# 12V_Buck_For_LDOs.net
KiCad netlist of a schematic drawn in Altium Designer
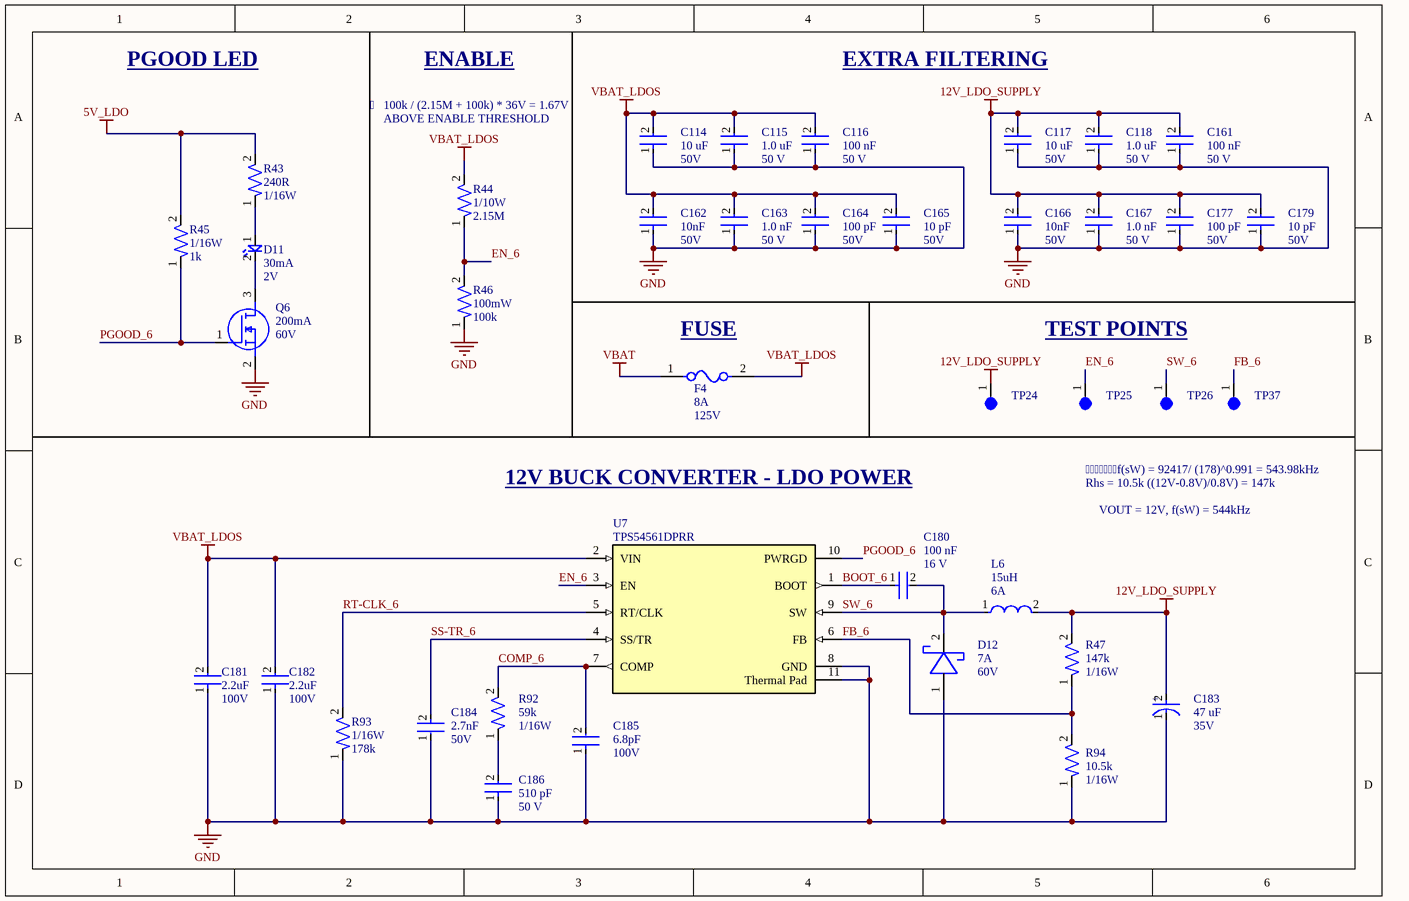
[diagram p0: 12V_Buck_For_LDOs.SchDoc]

(export (version "E")
  (design (tool "Eeschema 10.0.6"))
  (components
    (comp (ref "C114")
      (value "CL32B106KBJNNNE")
      (footprint "CAP-1210")
      (description "CAP CER 10UF 50V X7R 1210")
      (fields (field (name "VOLTAGE") "50V") (field (name "CAPACITANCE") "10 uF"))
      (libsource (lib "JLC_25") (part "CAP-10U-0002"))
    )
    (comp (ref "C115")
      (value "CC0805KKX7R9BB105")
      (footprint "CAP-0805")
      (description "CAP CER 1UF 50V X7R 0805")
      (fields (field (name "VOLTAGE") "50 V") (field (name "CAPACITANCE") "1.0 uF"))
      (libsource (lib "JLC_25") (part "CAP-1U-0001"))
    )
    (comp (ref "C116")
      (value "CC0805KRX7R9BB104")
      (footprint "CAP-0805")
      (description "CAP CER 0.1UF 50V X7R 0805")
      (fields (field (name "VOLTAGE RATING") "50 V") (field (name "CAPACITANCE") "100 nF"))
      (libsource (lib "JLC_25") (part "CAP-0.1U-0002"))
    )
    (comp (ref "C117")
      (value "CL32B106KBJNNNE")
      (footprint "CAP-1210")
      (description "CAP CER 10UF 50V X7R 1210")
      (fields (field (name "VOLTAGE") "50V") (field (name "CAPACITANCE") "10 uF"))
      (libsource (lib "JLC_25") (part "CAP-10U-0002"))
    )
    (comp (ref "C118")
      (value "CC0805KKX7R9BB105")
      (footprint "CAP-0805")
      (description "CAP CER 1UF 50V X7R 0805")
      (fields (field (name "VOLTAGE") "50 V") (field (name "CAPACITANCE") "1.0 uF"))
      (libsource (lib "JLC_25") (part "CAP-1U-0001"))
    )
    (comp (ref "C161")
      (value "CC0805KRX7R9BB104")
      (footprint "CAP-0805")
      (description "CAP CER 0.1UF 50V X7R 0805")
      (fields (field (name "VOLTAGE RATING") "50 V") (field (name "CAPACITANCE") "100 nF"))
      (libsource (lib "JLC_25") (part "CAP-0.1U-0002"))
    )
    (comp (ref "C162")
      (value "GRM2195C1H103JA01D")
      (footprint "CAP-0805")
      (description "CAP CER 10000PF 50V C0G/NP0 0805")
      (fields (field (name "VOLTAGE") "50V") (field (name "CAPACITANCE") "10nF"))
      (libsource (lib "JLC_25") (part "CAP-10N-0001"))
    )
    (comp (ref "C163")
      (value "CC0402KRX7R9BB102")
      (footprint "CAP-0402")
      (description "CAP CER 1000PF 50V X7R 0402")
      (fields (field (name "VOLTAGE") "50 V") (field (name "CAPACITANCE") "1.0 nF"))
      (libsource (lib "JLC_25") (part "CAP-1N-0001"))
    )
    (comp (ref "C164")
      (value "CC0402JRNPO9BN101")
      (footprint "CAP-0402")
      (description "CAP CER 100PF 50V C0G/NPO 0402")
      (fields (field (name "CAPACITANCE") "100 pF") (field (name "VOLTAGE") "50V"))
      (libsource (lib "JLC_25") (part "CAP-100P-0001"))
    )
    (comp (ref "C165")
      (value "CC0402JRNPO9BN100")
      (footprint "CAP-0402")
      (description "CAP CER 10PF 50V C0G/NPO 0402")
      (fields (field (name "CAPACITANCE") "10 pF") (field (name "VOLTAGE") "50V"))
      (libsource (lib "JLC_25") (part "CAP-10P-0001"))
    )
    (comp (ref "C166")
      (value "GRM2195C1H103JA01D")
      (footprint "CAP-0805")
      (description "CAP CER 10000PF 50V C0G/NP0 0805")
      (fields (field (name "VOLTAGE") "50V") (field (name "CAPACITANCE") "10nF"))
      (libsource (lib "JLC_25") (part "CAP-10N-0001"))
    )
    (comp (ref "C167")
      (value "CC0402KRX7R9BB102")
      (footprint "CAP-0402")
      (description "CAP CER 1000PF 50V X7R 0402")
      (fields (field (name "VOLTAGE") "50 V") (field (name "CAPACITANCE") "1.0 nF"))
      (libsource (lib "JLC_25") (part "CAP-1N-0001"))
    )
    (comp (ref "C177")
      (value "CC0402JRNPO9BN101")
      (footprint "CAP-0402")
      (description "CAP CER 100PF 50V C0G/NPO 0402")
      (fields (field (name "CAPACITANCE") "100 pF") (field (name "VOLTAGE") "50V"))
      (libsource (lib "JLC_25") (part "CAP-100P-0001"))
    )
    (comp (ref "C179")
      (value "CC0402JRNPO9BN100")
      (footprint "CAP-0402")
      (description "CAP CER 10PF 50V C0G/NPO 0402")
      (fields (field (name "CAPACITANCE") "10 pF") (field (name "VOLTAGE") "50V"))
      (libsource (lib "JLC_25") (part "CAP-10P-0001"))
    )
    (comp (ref "C180")
      (value "CC0402KRX7R7BB104")
      (footprint "CAP-0402")
      (description "CAP CER 0.1UF 16V X7R 0402")
      (fields (field (name "VOLTAGE RATING") "16 V") (field (name "CAPACITANCE") "100 nF"))
      (libsource (lib "JLC_25") (part "CAP-0.1U-0001"))
    )
    (comp (ref "C181")
      (value "CC1206KKX7R0BB225")
      (footprint "CAP-1206")
      (description "CAP CER 2.2UF 100V X7R 1206")
      (fields (field (name "CAPACITANCE") "2.2uF") (field (name "VOLTAGE") "100V"))
      (libsource (lib "JLC_25") (part "CAP-2.2U-0001"))
    )
    (comp (ref "C182")
      (value "CC1206KKX7R0BB225")
      (footprint "CAP-1206")
      (description "CAP CER 2.2UF 100V X7R 1206")
      (fields (field (name "CAPACITANCE") "2.2uF") (field (name "VOLTAGE") "100V"))
      (libsource (lib "JLC_25") (part "CAP-2.2U-0001"))
    )
    (comp (ref "C183")
      (value "EEH-ZC1V470P")
      (footprint "CAP_EEHZC1V470P")
      (description "47 µF 35 V Aluminum - Polymer Capacitors Radial, Can - SMD 60mOhm 4000 Hrs @ 125°C")
      (fields (field (name "VOLTAGE") "35V") (field (name "CAPACITANCE") "47 uF"))
      (libsource (lib "JLC_25") (part "CAP-47U-0003"))
    )
    (comp (ref "C184")
      (value "GRM2165C1H272JA01D")
      (footprint "CAP-0805")
      (description "CAP CER 2700PF 50V C0G/NP0 0805")
      (fields (field (name "VOLTAGE") "50V") (field (name "CAPACITANCE") "2.7nF"))
      (libsource (lib "JLC_25") (part "CAP-2.7N-0001"))
    )
    (comp (ref "C185")
      (value "CC0603CRNPO0BN6R8")
      (footprint "CAP-0603")
      (description "CAP CER 6.8PF 100V C0G/NPO 0603")
      (fields (field (name "VOLTAGE") "100V") (field (name "CAPACITANCE") "6.8pF"))
      (libsource (lib "JLC_25") (part "CAP-6.8P-0001"))
    )
    (comp (ref "C186")
      (value "0402N511J500CT")
      (footprint "CAP-0402")
      (description "CAP CER 510PF 50V C0G/NP0 0402")
      (fields (field (name "VOLTAGE") "50 V") (field (name "CAPACITANCE") "510 pF"))
      (libsource (lib "JLC_25") (part "CAP-510P-0001"))
    )
    (comp (ref "D11")
      (value "BL-HKC36G-AV-TRB")
      (footprint "LED-0603")
      (description "LED YELLOW CLEAR 0603 SMD")
      (fields (field (name "FORWARD CURRENT") "30mA") (field (name "FORWARD VOLTAGE") "2V"))
      (libsource (lib "JLC_25") (part "LED-0001"))
    )
    (comp (ref "D12")
      (value "PDS760-13")
      (footprint "DO-POWERDI5")
      (description "DIODE SCHOTTKY 60V 7A POWERDI5")
      (fields (field (name "FORWARD CURRENT") "7A") (field (name "REVERSE VOLTAGE (DC)") "60V"))
      (libsource (lib "JLC_25") (part "DIO-SCHOTTKY-0001"))
    )
    (comp (ref "F4")
      (value "01550900M")
      (footprint "FUSE-0001")
      (description "FUSE BLOK CARTRIDGE 125V 10A SMD")
      (fields (field (name "FUSE CURRENT") "8A") (field (name "VOLTAGE RATING") "125V"))
      (libsource (lib "JLC_25") (part "FUSE-0001"))
    )
    (comp (ref "L6")
      (value "CSAD1010-150M")
      (footprint "IND-15U-0002")
      (description "SMD MOLDING POWER CHOKE")
      (fields (field (name "INDUCTANCE") "15uH") (field (name "CURRENT RATING") "6A"))
      (libsource (lib "JLC_25") (part "IND-15U-0002-NoJLC"))
    )
    (comp (ref "Q6")
      (value "T2N7002AK,LM")
      (footprint "IC-SOT23-3")
      (description "MOSFET N-CH 60V 200MA SOT23")
      (fields (field (name "CONTINUOUS CURRENT") "200mA") (field (name "VOLTAGE") "60V"))
      (libsource (lib "JLC_25") (part "NMOS-200MA-0001"))
    )
    (comp (ref "R43")
      (value "RC0402FR-07240RL")
      (footprint "RES-0402")
      (description "240R 0.063W 1% 0402 (1005 Metric)  SMD")
      (fields
        (field (name "TOLERANCE") "1%")
        (field (name "RESISTANCE") "240R")
        (field (name "POWER") "1/16W")
      )
      (libsource (lib "JLC_25") (part "RES-240-0001"))
    )
    (comp (ref "R44")
      (value "RC0603FR-072M15L")
      (footprint "RES-0603")
      (description "RES SMD 2.15M OHM 1% 1/10W 0603")
      (fields
        (field (name "TOLERANCE") "1%")
        (field (name "POWER") "1/10W")
        (field (name "RESISTANCE") "2.15M")
      )
      (libsource (lib "JLC_25") (part "RES-2.15M-0001"))
    )
    (comp (ref "R45")
      (value "RC0402FR-071KL")
      (footprint "RES-0402")
      (description "RES 1K OHM 1% 1/16W 0402")
      (fields (field (name "TOLERANCE") "1%") (field (name "POWER") "1/16W") (field (name "RESISTANCE") "1k"))
      (libsource (lib "JLC_25") (part "RES-1k-0001"))
    )
    (comp (ref "R46")
      (value "RC0603FR-07100KL")
      (footprint "RES-0603")
      (description "RES SMD 100K OHM 1% 1/10W 0603")
      (fields
        (field (name "TOLERANCE") "1%")
        (field (name "POWER") "100mW")
        (field (name "RESISTANCE") "100k")
      )
      (libsource (lib "JLC_25") (part "RES-100k-0001"))
    )
    (comp (ref "R47")
      (value "RC0402FR-07147KL")
      (footprint "RES-0402")
      (description "RES 147K OHM 1% 1/16W 0402")
      (fields
        (field (name "TOLERANCE") "1%")
        (field (name "POWER") "1/16W")
        (field (name "RESISTANCE") "147k")
      )
      (libsource (lib "JLC_25") (part "RES-147k-0001"))
    )
    (comp (ref "R92")
      (value "RC0402FR-0759KL")
      (footprint "RES-0402")
      (description "RES 59K OHM 1% 1/16W 0402")
      (fields
        (field (name "TOLERANCE") "1%")
        (field (name "POWER") "1/16W")
        (field (name "RESISTANCE") "59k")
      )
      (libsource (lib "JLC_25") (part "RES-59k-0001"))
    )
    (comp (ref "R93")
      (value "RTT021783FTH")
      (footprint "RES-0402")
      (description "62.5mW Thick Film Resistors 50V ±100ppm/℃ ±1% 178kΩ 0402 Chip Resistor - Surface Mount ROHS")
      (fields
        (field (name "TOLERANCE") "1%")
        (field (name "POWER") "1/16W")
        (field (name "RESISTANCE") "178k")
      )
      (libsource (lib "JLC_25") (part "RES-178k-0001_1"))
    )
    (comp (ref "R94")
      (value "RC0402FR-0710K5L")
      (footprint "RES-0402")
      (description "RES 10.5K OHM 1% 1/16W 0402")
      (fields
        (field (name "TOLERANCE") "1%")
        (field (name "POWER") "1/16W")
        (field (name "RESISTANCE") "10.5k")
      )
      (libsource (lib "JLC_25") (part "RES-10.5k-0001"))
    )
    (comp (ref "TP24")
      (value "5003")
      (footprint "TEST-POINT-0001")
      (description "Oranange PC Test Point, Miniature Phoisphor Bronze Silver Plating Through Hole Mounting Type")
      (libsource (lib "*") (part "TEST-POINT-0001"))
    )
    (comp (ref "TP25")
      (value "5003")
      (footprint "TEST-POINT-0001")
      (description "Oranange PC Test Point, Miniature Phoisphor Bronze Silver Plating Through Hole Mounting Type")
      (libsource (lib "*") (part "TEST-POINT-0001"))
    )
    (comp (ref "TP26")
      (value "5003")
      (footprint "TEST-POINT-0001")
      (description "Oranange PC Test Point, Miniature Phoisphor Bronze Silver Plating Through Hole Mounting Type")
      (libsource (lib "*") (part "TEST-POINT-0001"))
    )
    (comp (ref "TP37")
      (value "5003")
      (footprint "TEST-POINT-0001")
      (description "Oranange PC Test Point, Miniature Phoisphor Bronze Silver Plating Through Hole Mounting Type")
      (libsource (lib "*") (part "TEST-POINT-0001"))
    )
    (comp (ref "U7")
      (value "TPS54561DPRR")
      (footprint "IC-10WSON")
      (description "IC REG BUCK ADJ 5A 10WSON")
      (libsource (lib "JLC_25") (part "IC-BUCK-0001"))
    )
  )
  (nets
    (net (code "1") (name "/BOOT_6") (class "Default")
      (node (ref "C180") (pin "1") (pinfunction "1_1") (pintype "passive"))
      (node (ref "U7") (pin "1") (pinfunction "BOOT_1") (pintype "output"))
    )
    (net (code "2") (name "/COMP_6") (class "Default")
      (node (ref "C185") (pin "2") (pinfunction "2_2") (pintype "passive"))
      (node (ref "R92") (pin "2") (pinfunction "2_2") (pintype "passive"))
      (node (ref "U7") (pin "7") (pinfunction "COMP_7") (pintype "output"))
    )
    (net (code "3") (name "/EN_6") (class "Default")
      (node (ref "R44") (pin "1") (pinfunction "1_1") (pintype "passive"))
      (node (ref "R46") (pin "2") (pinfunction "2_2") (pintype "passive"))
      (node (ref "TP25") (pin "1") (pinfunction "0_1") (pintype "passive"))
      (node (ref "U7") (pin "3") (pinfunction "EN_3") (pintype "input"))
    )
    (net (code "4") (name "/FB_6") (class "Default")
      (node (ref "R47") (pin "1") (pinfunction "1_1") (pintype "passive"))
      (node (ref "R94") (pin "2") (pinfunction "2_2") (pintype "passive"))
      (node (ref "TP37") (pin "1") (pinfunction "0_1") (pintype "passive"))
      (node (ref "U7") (pin "6") (pinfunction "FB_6") (pintype "input"))
    )
    (net (code "5") (name "/PGOOD_6") (class "Default")
      (node (ref "Q6") (pin "1") (pinfunction "G_1") (pintype "passive"))
      (node (ref "R45") (pin "1") (pinfunction "1_1") (pintype "passive"))
      (node (ref "U7") (pin "10") (pinfunction "PWRGD_10") (pintype "open_collector"))
    )
    (net (code "6") (name "/RT-CLK_6") (class "Default")
      (node (ref "R93") (pin "2") (pinfunction "2_2") (pintype "passive"))
      (node (ref "U7") (pin "5") (pinfunction "RT/CLK_5") (pintype "input"))
    )
    (net (code "7") (name "/SS-TR_6") (class "Default")
      (node (ref "C184") (pin "2") (pinfunction "2_2") (pintype "passive"))
      (node (ref "U7") (pin "4") (pinfunction "SS/TR_4") (pintype "input"))
    )
    (net (code "8") (name "/SW_6") (class "Default")
      (node (ref "C180") (pin "2") (pinfunction "2_2") (pintype "passive"))
      (node (ref "D12") (pin "2") (pinfunction "ANODE_2") (pintype "passive"))
      (node (ref "L6") (pin "1") (pinfunction "1_1") (pintype "passive"))
      (node (ref "TP26") (pin "1") (pinfunction "0_1") (pintype "passive"))
      (node (ref "U7") (pin "9") (pinfunction "SW_9") (pintype "input"))
    )
    (net (code "9") (name "5V_LDO") (class "Default")
      (node (ref "R43") (pin "2") (pinfunction "2_2") (pintype "passive"))
      (node (ref "R45") (pin "2") (pinfunction "2_2") (pintype "passive"))
    )
    (net (code "10") (name "12V_LDO_SUPPLY") (class "Default")
      (node (ref "C117") (pin "2") (pinfunction "2_2") (pintype "passive"))
      (node (ref "C118") (pin "2") (pinfunction "2_2") (pintype "passive"))
      (node (ref "C161") (pin "2") (pinfunction "2_2") (pintype "passive"))
      (node (ref "C166") (pin "2") (pinfunction "2_2") (pintype "passive"))
      (node (ref "C167") (pin "2") (pinfunction "2_2") (pintype "passive"))
      (node (ref "C177") (pin "2") (pinfunction "2_2") (pintype "passive"))
      (node (ref "C179") (pin "2") (pinfunction "2_2") (pintype "passive"))
      (node (ref "C183") (pin "2") (pinfunction "A_2") (pintype "passive"))
      (node (ref "L6") (pin "2") (pinfunction "2_2") (pintype "passive"))
      (node (ref "R47") (pin "2") (pinfunction "2_2") (pintype "passive"))
      (node (ref "TP24") (pin "1") (pinfunction "0_1") (pintype "passive"))
    )
    (net (code "11") (name "GND") (class "Default")
      (node (ref "C114") (pin "1") (pinfunction "1_1") (pintype "passive"))
      (node (ref "C115") (pin "1") (pinfunction "1_1") (pintype "passive"))
      (node (ref "C116") (pin "1") (pinfunction "1_1") (pintype "passive"))
      (node (ref "C117") (pin "1") (pinfunction "1_1") (pintype "passive"))
      (node (ref "C118") (pin "1") (pinfunction "1_1") (pintype "passive"))
      (node (ref "C161") (pin "1") (pinfunction "1_1") (pintype "passive"))
      (node (ref "C162") (pin "1") (pinfunction "1_1") (pintype "passive"))
      (node (ref "C163") (pin "1") (pinfunction "1_1") (pintype "passive"))
      (node (ref "C164") (pin "1") (pinfunction "1_1") (pintype "passive"))
      (node (ref "C165") (pin "1") (pinfunction "1_1") (pintype "passive"))
      (node (ref "C166") (pin "1") (pinfunction "1_1") (pintype "passive"))
      (node (ref "C167") (pin "1") (pinfunction "1_1") (pintype "passive"))
      (node (ref "C177") (pin "1") (pinfunction "1_1") (pintype "passive"))
      (node (ref "C179") (pin "1") (pinfunction "1_1") (pintype "passive"))
      (node (ref "C181") (pin "1") (pinfunction "1_1") (pintype "passive"))
      (node (ref "C182") (pin "1") (pinfunction "1_1") (pintype "passive"))
      (node (ref "C183") (pin "1") (pinfunction "C_1") (pintype "passive"))
      (node (ref "C184") (pin "1") (pinfunction "1_1") (pintype "passive"))
      (node (ref "C185") (pin "1") (pinfunction "1_1") (pintype "passive"))
      (node (ref "C186") (pin "1") (pinfunction "1_1") (pintype "passive"))
      (node (ref "D12") (pin "1") (pinfunction "CATHODE_1") (pintype "passive"))
      (node (ref "Q6") (pin "2") (pinfunction "S_2") (pintype "passive"))
      (node (ref "R46") (pin "1") (pinfunction "1_1") (pintype "passive"))
      (node (ref "R93") (pin "1") (pinfunction "1_1") (pintype "passive"))
      (node (ref "R94") (pin "1") (pinfunction "1_1") (pintype "passive"))
      (node (ref "U7") (pin "11") (pinfunction "Thermal_Pad_11") (pintype "power_in"))
      (node (ref "U7") (pin "8") (pinfunction "GND_8") (pintype "power_in"))
    )
    (net (code "12") (name "Net-(C186-Pad2)") (class "Default")
      (node (ref "C186") (pin "2") (pinfunction "2_2") (pintype "passive"))
      (node (ref "R92") (pin "1") (pinfunction "1_1") (pintype "passive"))
    )
    (net (code "13") (name "Net-(D11-Pad1)") (class "Default")
      (node (ref "D11") (pin "1") (pinfunction "1_1") (pintype "passive"))
      (node (ref "R43") (pin "1") (pinfunction "1_1") (pintype "passive"))
    )
    (net (code "14") (name "Net-(Q6-D)") (class "Default")
      (node (ref "D11") (pin "2") (pinfunction "2_2") (pintype "passive"))
      (node (ref "Q6") (pin "3") (pinfunction "D_3") (pintype "passive"))
    )
    (net (code "15") (name "VBAT") (class "Default")
      (node (ref "F4") (pin "1") (pinfunction "1_1") (pintype "passive"))
    )
    (net (code "16") (name "VBAT_LDOS") (class "Default")
      (node (ref "C114") (pin "2") (pinfunction "2_2") (pintype "passive"))
      (node (ref "C115") (pin "2") (pinfunction "2_2") (pintype "passive"))
      (node (ref "C116") (pin "2") (pinfunction "2_2") (pintype "passive"))
      (node (ref "C162") (pin "2") (pinfunction "2_2") (pintype "passive"))
      (node (ref "C163") (pin "2") (pinfunction "2_2") (pintype "passive"))
      (node (ref "C164") (pin "2") (pinfunction "2_2") (pintype "passive"))
      (node (ref "C165") (pin "2") (pinfunction "2_2") (pintype "passive"))
      (node (ref "C181") (pin "2") (pinfunction "2_2") (pintype "passive"))
      (node (ref "C182") (pin "2") (pinfunction "2_2") (pintype "passive"))
      (node (ref "F4") (pin "2") (pinfunction "2_2") (pintype "passive"))
      (node (ref "R44") (pin "2") (pinfunction "2_2") (pintype "passive"))
      (node (ref "U7") (pin "2") (pinfunction "VIN_2") (pintype "input"))
    )
  )
)
